# Sequantial_Cell_Switching.net
KiCad netlist of a schematic drawn in Altium Designer
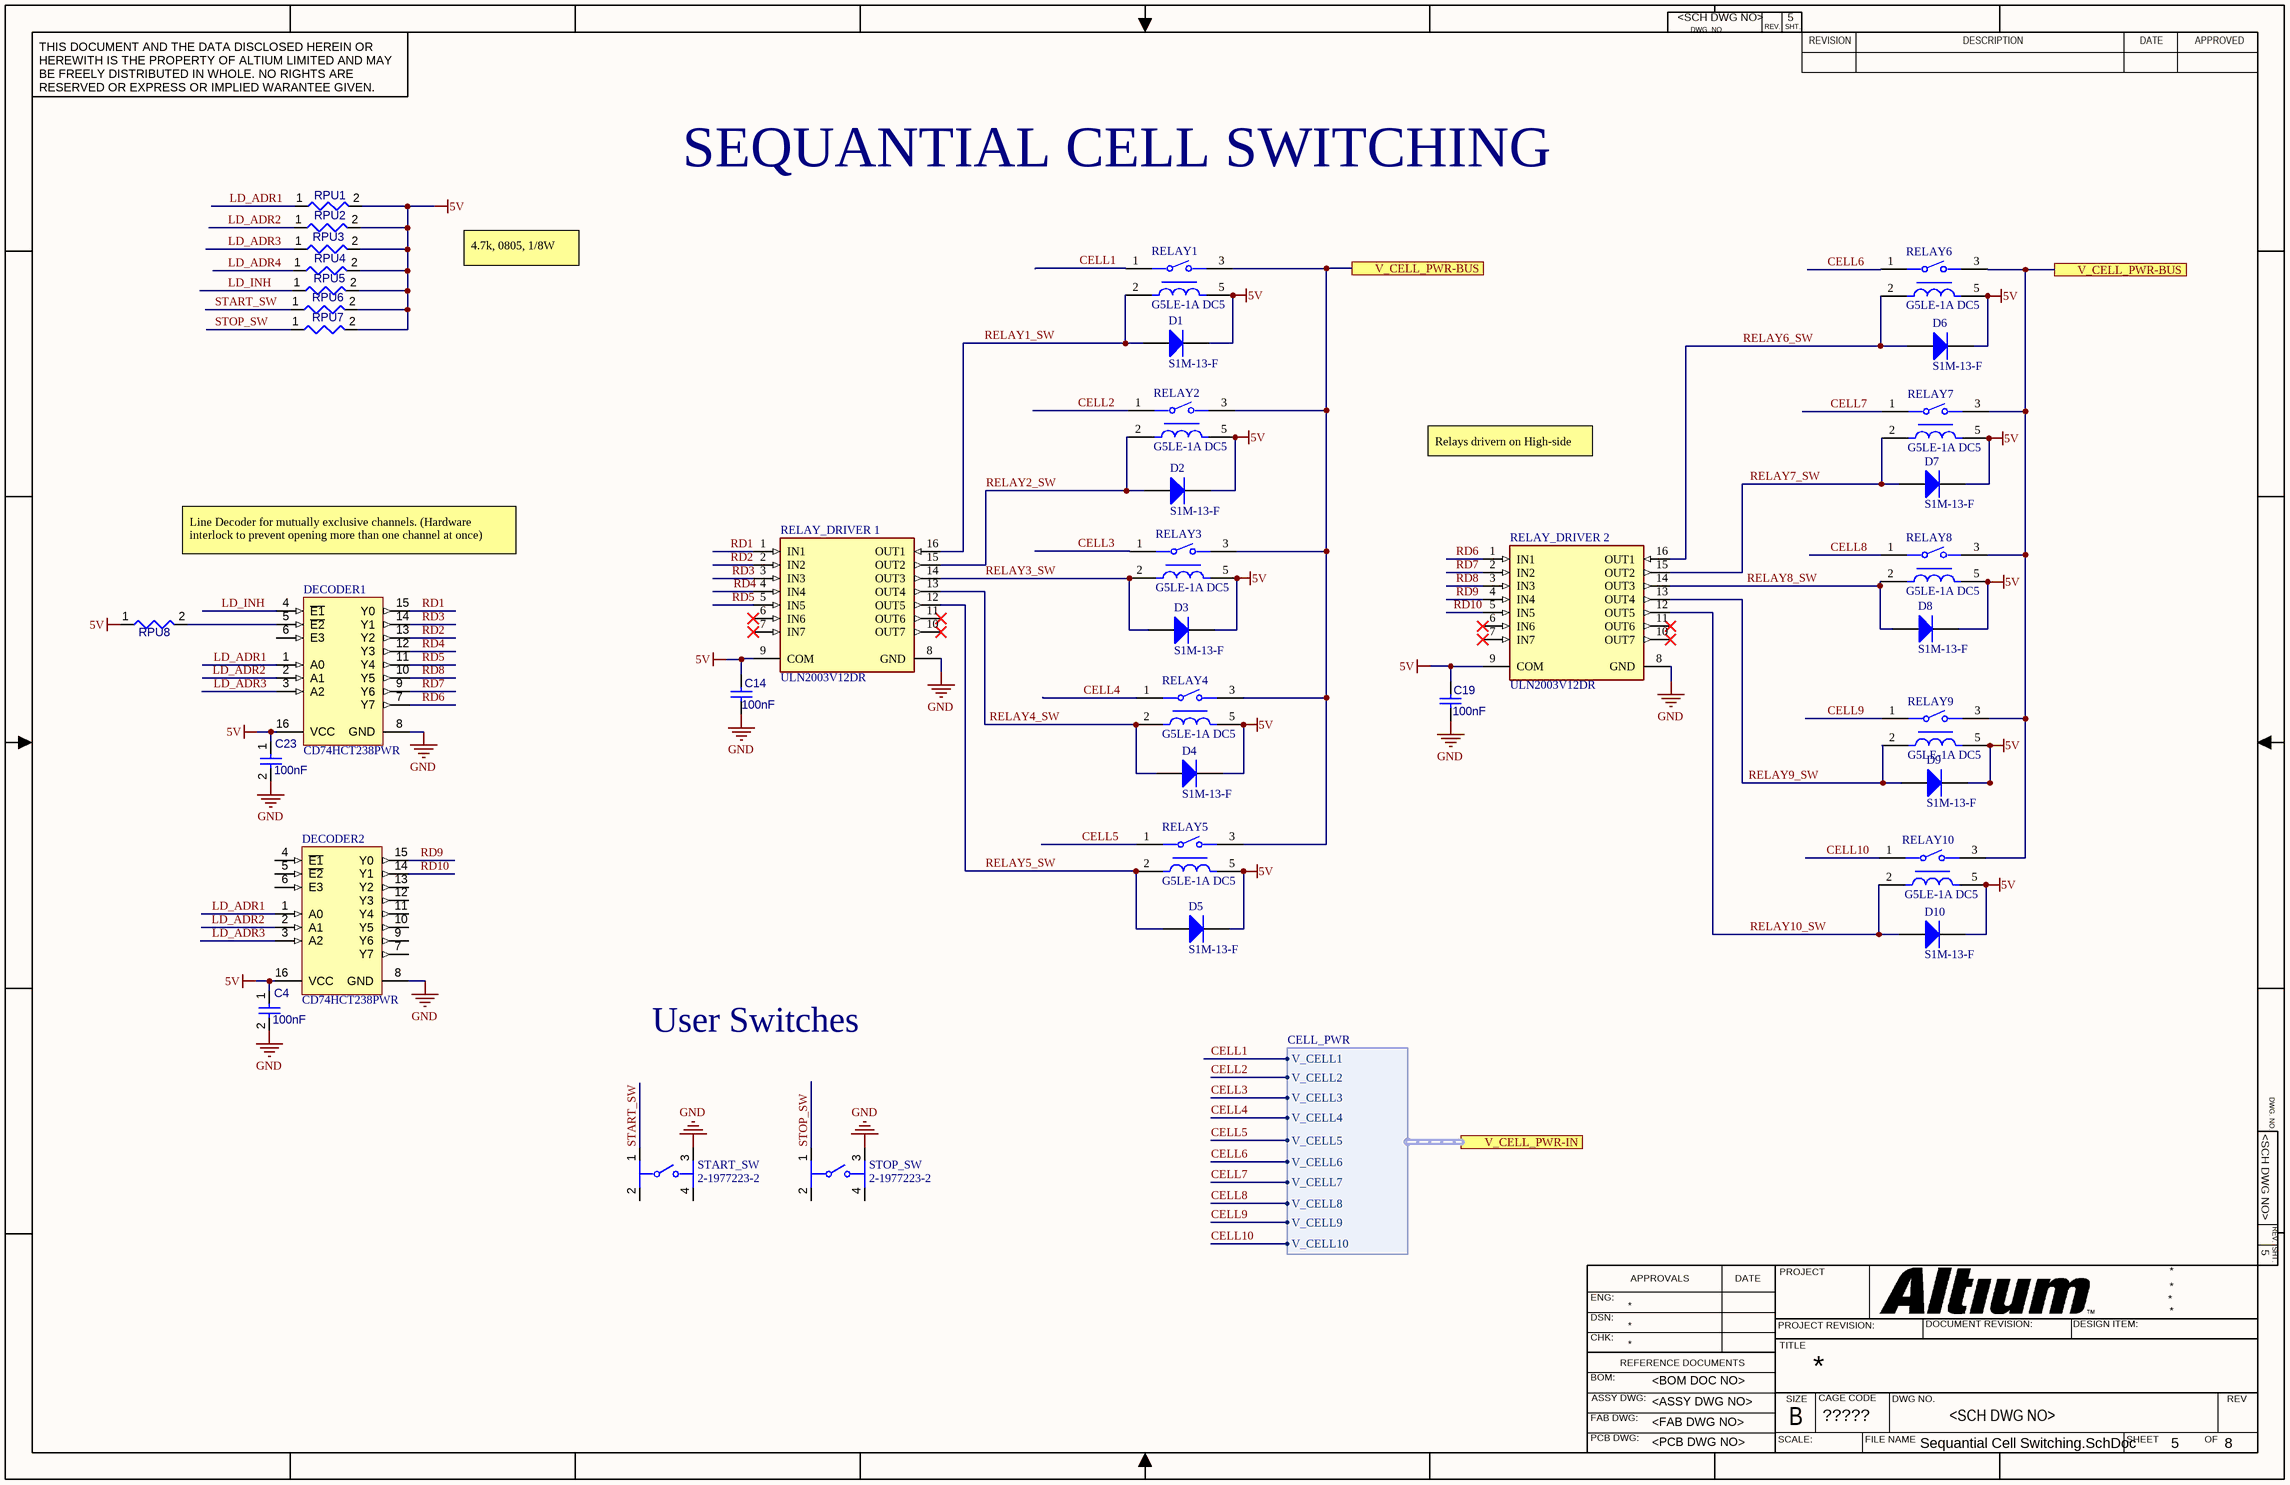
[diagram p0: Sequantial Cell Switching.SchDoc]

(export (version "E")
  (design (tool "Eeschema 10.0.6"))
  (components
    (comp (ref "C4")
      (value "100nF")
      (footprint "CAPC2013X95X50LL10T25")
      (description "Capacitor 100 nF +/-10% 50 V 0805")
      (fields (field (name "TOLERANCE") "10%"))
      (libsource (lib "gugan Sivakumar") (part "CAP-NP-2"))
    )
    (comp (ref "C14")
      (value "100nF")
      (footprint "CAPC2013X95X50LL10T25")
      (description "Capacitor 100 nF +/-10% 50 V 0805")
      (fields (field (name "TOLERANCE") "10%"))
      (libsource (lib "") (part "CAP-NP-2_1"))
    )
    (comp (ref "C19")
      (value "100nF")
      (footprint "CAPC2013X95X50LL10T25")
      (description "Capacitor 100 nF +/-10% 50 V 0805")
      (fields (field (name "TOLERANCE") "10%"))
      (libsource (lib "") (part "CAP-NP-2_1"))
    )
    (comp (ref "C23")
      (value "100nF")
      (footprint "CAPC2013X95X50LL10T25")
      (description "Capacitor 100 nF +/-10% 50 V 0805")
      (fields (field (name "TOLERANCE") "10%"))
      (libsource (lib "gugan Sivakumar") (part "CAP-NP-2"))
    )
    (comp (ref "D1")
      (value "S1M-13-F")
      (footprint "DIOD-S1M-13-F-SMA-2_V")
      (fields (field (name "MANUFACTURER") "Diodes Inc"))
      (libsource (lib "Altium Content Vault") (part "DIOD-D-A1K2-2"))
    )
    (comp (ref "D2")
      (value "S1M-13-F")
      (footprint "DIOD-S1M-13-F-SMA-2_V")
      (fields (field (name "MANUFACTURER") "Diodes Inc"))
      (libsource (lib "Altium Content Vault") (part "DIOD-D-A1K2-2"))
    )
    (comp (ref "D3")
      (value "S1M-13-F")
      (footprint "DIOD-S1M-13-F-SMA-2_V")
      (fields (field (name "MANUFACTURER") "Diodes Inc"))
      (libsource (lib "Altium Content Vault") (part "DIOD-D-A1K2-2"))
    )
    (comp (ref "D4")
      (value "S1M-13-F")
      (footprint "DIOD-S1M-13-F-SMA-2_V")
      (fields (field (name "MANUFACTURER") "Diodes Inc"))
      (libsource (lib "Altium Content Vault") (part "DIOD-D-A1K2-2"))
    )
    (comp (ref "D5")
      (value "S1M-13-F")
      (footprint "DIOD-S1M-13-F-SMA-2_V")
      (fields (field (name "MANUFACTURER") "Diodes Inc"))
      (libsource (lib "Altium Content Vault") (part "DIOD-D-A1K2-2"))
    )
    (comp (ref "D6")
      (value "S1M-13-F")
      (footprint "DIOD-S1M-13-F-SMA-2_V")
      (fields (field (name "MANUFACTURER") "Diodes Inc"))
      (libsource (lib "Altium Content Vault") (part "DIOD-D-A1K2-2"))
    )
    (comp (ref "D7")
      (value "S1M-13-F")
      (footprint "DIOD-S1M-13-F-SMA-2_V")
      (fields (field (name "MANUFACTURER") "Diodes Inc"))
      (libsource (lib "Altium Content Vault") (part "DIOD-D-A1K2-2"))
    )
    (comp (ref "D8")
      (value "S1M-13-F")
      (footprint "DIOD-S1M-13-F-SMA-2_V")
      (fields (field (name "MANUFACTURER") "Diodes Inc"))
      (libsource (lib "Altium Content Vault") (part "DIOD-D-A1K2-2"))
    )
    (comp (ref "D9")
      (value "S1M-13-F")
      (footprint "DIOD-S1M-13-F-SMA-2_V")
      (fields (field (name "MANUFACTURER") "Diodes Inc"))
      (libsource (lib "Altium Content Vault") (part "DIOD-D-A1K2-2"))
    )
    (comp (ref "D10")
      (value "S1M-13-F")
      (footprint "DIOD-S1M-13-F-SMA-2_V")
      (fields (field (name "MANUFACTURER") "Diodes Inc"))
      (libsource (lib "Altium Content Vault") (part "DIOD-D-A1K2-2"))
    )
    (comp (ref "DECODER1")
      (value "CD74HCT238PWR")
      (footprint "PW0016A_L")
      (fields
        (field (name "MANUFACTURER") "Texas Instruments")
        (field (name "GENERIC PART NUMBER") "CD74HCT238")
      )
      (libsource (lib "Altium Content Vault") (part "TI-CD54_74HCX238-16"))
    )
    (comp (ref "DECODER2")
      (value "CD74HCT238PWR")
      (footprint "PW0016A_L")
      (fields
        (field (name "MANUFACTURER") "Texas Instruments")
        (field (name "GENERIC PART NUMBER") "CD74HCT238")
      )
      (libsource (lib "Altium Content Vault") (part "TI-CD54_74HCX238-16"))
    )
    (comp (ref "RELAY1")
      (value "G5LE-1A DC5")
      (footprint "FP-G5LE-1A_DC5-MFG")
      (description "RELAY GEN PURPOSE SPST 10A 5V")
      (libsource (lib "Altium Content Vault") (part "6e495d724dc645a58f977e2129b87ff"))
    )
    (comp (ref "RELAY2")
      (value "G5LE-1A DC5")
      (footprint "FP-G5LE-1A_DC5-MFG")
      (description "RELAY GEN PURPOSE SPST 10A 5V")
      (libsource (lib "Altium Content Vault") (part "6e495d724dc645a58f977e2129b87ff"))
    )
    (comp (ref "RELAY3")
      (value "G5LE-1A DC5")
      (footprint "FP-G5LE-1A_DC5-MFG")
      (description "RELAY GEN PURPOSE SPST 10A 5V")
      (libsource (lib "Altium Content Vault") (part "6e495d724dc645a58f977e2129b87ff"))
    )
    (comp (ref "RELAY4")
      (value "G5LE-1A DC5")
      (footprint "FP-G5LE-1A_DC5-MFG")
      (description "RELAY GEN PURPOSE SPST 10A 5V")
      (libsource (lib "Altium Content Vault") (part "6e495d724dc645a58f977e2129b87ff"))
    )
    (comp (ref "RELAY5")
      (value "G5LE-1A DC5")
      (footprint "FP-G5LE-1A_DC5-MFG")
      (description "RELAY GEN PURPOSE SPST 10A 5V")
      (libsource (lib "Altium Content Vault") (part "6e495d724dc645a58f977e2129b87ff"))
    )
    (comp (ref "RELAY6")
      (value "G5LE-1A DC5")
      (footprint "FP-G5LE-1A_DC5-MFG")
      (description "RELAY GEN PURPOSE SPST 10A 5V")
      (libsource (lib "Altium Content Vault") (part "6e495d724dc645a58f977e2129b87ff"))
    )
    (comp (ref "RELAY7")
      (value "G5LE-1A DC5")
      (footprint "FP-G5LE-1A_DC5-MFG")
      (description "RELAY GEN PURPOSE SPST 10A 5V")
      (libsource (lib "Altium Content Vault") (part "6e495d724dc645a58f977e2129b87ff"))
    )
    (comp (ref "RELAY8")
      (value "G5LE-1A DC5")
      (footprint "FP-G5LE-1A_DC5-MFG")
      (description "RELAY GEN PURPOSE SPST 10A 5V")
      (libsource (lib "Altium Content Vault") (part "6e495d724dc645a58f977e2129b87ff"))
    )
    (comp (ref "RELAY9")
      (value "G5LE-1A DC5")
      (footprint "FP-G5LE-1A_DC5-MFG")
      (description "RELAY GEN PURPOSE SPST 10A 5V")
      (libsource (lib "Altium Content Vault") (part "6e495d724dc645a58f977e2129b87ff"))
    )
    (comp (ref "RELAY10")
      (value "G5LE-1A DC5")
      (footprint "FP-G5LE-1A_DC5-MFG")
      (description "RELAY GEN PURPOSE SPST 10A 5V")
      (libsource (lib "Altium Content Vault") (part "6e495d724dc645a58f977e2129b87ff"))
    )
    (comp (ref "RELAY_DRIVER 1")
      (value "ULN2003V12DR")
      (footprint "FP-D0016A-MFG")
      (description "MOSFET 7CH 16SOIC")
      (libsource (lib "Altium Content Vault") (part "1bf5c18f3aeaca83cb90dec63c1b343"))
    )
    (comp (ref "RELAY_DRIVER 2")
      (value "ULN2003V12DR")
      (footprint "FP-D0016A-MFG")
      (description "MOSFET 7CH 16SOIC")
      (libsource (lib "Altium Content Vault") (part "1bf5c18f3aeaca83cb90dec63c1b343"))
    )
    (comp (ref "RPU1")
      (value "Resistor 4k7 +/-1% 0805 125 mW")
      (footprint "RESC2013X70X40ML20T20")
      (description "Chip Resistor, 4.7 KOhm, +/- 1%, 0.125 W, -55 to 155 degC, 0805 (2012 Metric)")
      (fields (field (name "TOLERANCE") "1%") (field (name "POWER") "125mW"))
      (libsource (lib "gugan Sivakumar") (part "RES-2"))
    )
    (comp (ref "RPU2")
      (value "Resistor 4k7 +/-1% 0805 125 mW")
      (footprint "RESC2013X70X40ML20T20")
      (description "Chip Resistor, 4.7 KOhm, +/- 1%, 0.125 W, -55 to 155 degC, 0805 (2012 Metric)")
      (fields (field (name "TOLERANCE") "1%") (field (name "POWER") "125mW"))
      (libsource (lib "gugan Sivakumar") (part "RES-2"))
    )
    (comp (ref "RPU3")
      (value "Resistor 4k7 +/-1% 0805 125 mW")
      (footprint "RESC2013X70X40ML20T20")
      (description "Chip Resistor, 4.7 KOhm, +/- 1%, 0.125 W, -55 to 155 degC, 0805 (2012 Metric)")
      (fields (field (name "TOLERANCE") "1%") (field (name "POWER") "125mW"))
      (libsource (lib "gugan Sivakumar") (part "RES-2"))
    )
    (comp (ref "RPU4")
      (value "Resistor 4k7 +/-1% 0805 125 mW")
      (footprint "RESC2013X70X40ML20T20")
      (description "Chip Resistor, 4.7 KOhm, +/- 1%, 0.125 W, -55 to 155 degC, 0805 (2012 Metric)")
      (fields (field (name "TOLERANCE") "1%") (field (name "POWER") "125mW"))
      (libsource (lib "gugan Sivakumar") (part "RES-2"))
    )
    (comp (ref "RPU5")
      (value "Resistor 4k7 +/-1% 0805 125 mW")
      (footprint "RESC2013X70X40ML20T20")
      (description "Chip Resistor, 4.7 KOhm, +/- 1%, 0.125 W, -55 to 155 degC, 0805 (2012 Metric)")
      (fields (field (name "TOLERANCE") "1%") (field (name "POWER") "125mW"))
      (libsource (lib "gugan Sivakumar") (part "RES-2"))
    )
    (comp (ref "RPU6")
      (value "Resistor 4k7 +/-1% 0805 125 mW")
      (footprint "RESC2013X70X40ML20T20")
      (description "Chip Resistor, 4.7 KOhm, +/- 1%, 0.125 W, -55 to 155 degC, 0805 (2012 Metric)")
      (fields (field (name "TOLERANCE") "1%") (field (name "POWER") "125mW"))
      (libsource (lib "gugan Sivakumar") (part "RES-2"))
    )
    (comp (ref "RPU7")
      (value "Resistor 4k7 +/-1% 0805 125 mW")
      (footprint "RESC2013X70X40ML20T20")
      (description "Chip Resistor, 4.7 KOhm, +/- 1%, 0.125 W, -55 to 155 degC, 0805 (2012 Metric)")
      (fields (field (name "TOLERANCE") "1%") (field (name "POWER") "125mW"))
      (libsource (lib "gugan Sivakumar") (part "RES-2"))
    )
    (comp (ref "RPU8")
      (value "Resistor 4k7 +/-1% 0805 125 mW")
      (footprint "RESC2013X70X40ML20T20")
      (description "Chip Resistor, 4.7 KOhm, +/- 1%, 0.125 W, -55 to 155 degC, 0805 (2012 Metric)")
      (fields (field (name "TOLERANCE") "1%") (field (name "POWER") "125mW"))
      (libsource (lib "gugan Sivakumar") (part "RES-2"))
    )
    (comp (ref "START_SW")
      (value "2-1977223-2")
      (footprint "FP-2-1977223-2-MFG")
      (description "SWITCH TACTILE SPST-NO 0.05A 24V")
      (libsource (lib "Altium Content Vault") (part "b8895f3f4cefb76e1819d2863dba89b"))
    )
    (comp (ref "STOP_SW")
      (value "2-1977223-2")
      (footprint "FP-2-1977223-2-MFG")
      (description "SWITCH TACTILE SPST-NO 0.05A 24V")
      (libsource (lib "Altium Content Vault") (part "b8895f3f4cefb76e1819d2863dba89b"))
    )
  )
  (nets
    (net (code "2") (name "/CELL1") (class "Default")
      (node (ref "RELAY1") (pin "1") (pinfunction "1_1") (pintype "passive"))
    )
    (net (code "3") (name "/CELL2") (class "Default")
      (node (ref "RELAY2") (pin "1") (pinfunction "1_1") (pintype "passive"))
    )
    (net (code "4") (name "/CELL3") (class "Default")
      (node (ref "RELAY3") (pin "1") (pinfunction "1_1") (pintype "passive"))
    )
    (net (code "5") (name "/CELL4") (class "Default")
      (node (ref "RELAY4") (pin "1") (pinfunction "1_1") (pintype "passive"))
    )
    (net (code "6") (name "/CELL5") (class "Default")
      (node (ref "RELAY5") (pin "1") (pinfunction "1_1") (pintype "passive"))
    )
    (net (code "7") (name "/CELL6") (class "Default")
      (node (ref "RELAY6") (pin "1") (pinfunction "1_1") (pintype "passive"))
    )
    (net (code "8") (name "/CELL7") (class "Default")
      (node (ref "RELAY7") (pin "1") (pinfunction "1_1") (pintype "passive"))
    )
    (net (code "9") (name "/CELL8") (class "Default")
      (node (ref "RELAY8") (pin "1") (pinfunction "1_1") (pintype "passive"))
    )
    (net (code "10") (name "/CELL9") (class "Default")
      (node (ref "RELAY9") (pin "1") (pinfunction "1_1") (pintype "passive"))
    )
    (net (code "11") (name "/CELL10") (class "Default")
      (node (ref "RELAY10") (pin "1") (pinfunction "1_1") (pintype "passive"))
    )
    (net (code "12") (name "/LD_ADR1") (class "Default")
      (node (ref "DECODER1") (pin "1") (pinfunction "A0_1") (pintype "input"))
      (node (ref "DECODER2") (pin "1") (pinfunction "A0_1") (pintype "input"))
      (node (ref "RPU1") (pin "1") (pinfunction "1_1") (pintype "passive"))
    )
    (net (code "13") (name "/LD_ADR2") (class "Default")
      (node (ref "DECODER1") (pin "2") (pinfunction "A1_2") (pintype "input"))
      (node (ref "DECODER2") (pin "2") (pinfunction "A1_2") (pintype "input"))
      (node (ref "RPU2") (pin "1") (pinfunction "1_1") (pintype "passive"))
    )
    (net (code "14") (name "/LD_ADR3") (class "Default")
      (node (ref "DECODER1") (pin "3") (pinfunction "A2_3") (pintype "input"))
      (node (ref "DECODER2") (pin "3") (pinfunction "A2_3") (pintype "input"))
      (node (ref "RPU3") (pin "1") (pinfunction "1_1") (pintype "passive"))
    )
    (net (code "15") (name "/LD_ADR4") (class "Default")
      (node (ref "RPU4") (pin "1") (pinfunction "1_1") (pintype "passive"))
    )
    (net (code "16") (name "/LD_INH") (class "Default")
      (node (ref "DECODER1") (pin "4") (pinfunction "~{E1}_4") (pintype "input"))
      (node (ref "RPU5") (pin "1") (pinfunction "1_1") (pintype "passive"))
    )
    (net (code "17") (name "/RD1") (class "Default")
      (node (ref "DECODER1") (pin "15") (pinfunction "Y0_15") (pintype "output"))
      (node (ref "RELAY_DRIVER 1") (pin "1") (pinfunction "IN1_1") (pintype "input"))
    )
    (net (code "18") (name "/RD2") (class "Default")
      (node (ref "DECODER1") (pin "13") (pinfunction "Y2_13") (pintype "output"))
      (node (ref "RELAY_DRIVER 1") (pin "2") (pinfunction "IN2_2") (pintype "input"))
    )
    (net (code "19") (name "/RD3") (class "Default")
      (node (ref "DECODER1") (pin "14") (pinfunction "Y1_14") (pintype "output"))
      (node (ref "RELAY_DRIVER 1") (pin "3") (pinfunction "IN3_3") (pintype "input"))
    )
    (net (code "20") (name "/RD4") (class "Default")
      (node (ref "DECODER1") (pin "12") (pinfunction "Y3_12") (pintype "output"))
      (node (ref "RELAY_DRIVER 1") (pin "4") (pinfunction "IN4_4") (pintype "input"))
    )
    (net (code "21") (name "/RD5") (class "Default")
      (node (ref "DECODER1") (pin "11") (pinfunction "Y4_11") (pintype "output"))
      (node (ref "RELAY_DRIVER 1") (pin "5") (pinfunction "IN5_5") (pintype "input"))
    )
    (net (code "22") (name "/RD6") (class "Default")
      (node (ref "DECODER1") (pin "7") (pinfunction "Y7_7") (pintype "output"))
      (node (ref "RELAY_DRIVER 2") (pin "1") (pinfunction "IN1_1") (pintype "input"))
    )
    (net (code "23") (name "/RD7") (class "Default")
      (node (ref "DECODER1") (pin "9") (pinfunction "Y6_9") (pintype "output"))
      (node (ref "RELAY_DRIVER 2") (pin "2") (pinfunction "IN2_2") (pintype "input"))
    )
    (net (code "24") (name "/RD8") (class "Default")
      (node (ref "DECODER1") (pin "10") (pinfunction "Y5_10") (pintype "output"))
      (node (ref "RELAY_DRIVER 2") (pin "3") (pinfunction "IN3_3") (pintype "input"))
    )
    (net (code "25") (name "/RD9") (class "Default")
      (node (ref "DECODER2") (pin "15") (pinfunction "Y0_15") (pintype "output"))
      (node (ref "RELAY_DRIVER 2") (pin "4") (pinfunction "IN4_4") (pintype "input"))
    )
    (net (code "26") (name "/RD10") (class "Default")
      (node (ref "DECODER2") (pin "14") (pinfunction "Y1_14") (pintype "output"))
      (node (ref "RELAY_DRIVER 2") (pin "5") (pinfunction "IN5_5") (pintype "input"))
    )
    (net (code "27") (name "/RELAY1_SW") (class "Default")
      (node (ref "D1") (pin "1") (pinfunction "A_1") (pintype "passive"))
      (node (ref "RELAY1") (pin "2") (pinfunction "2_2") (pintype "passive"))
      (node (ref "RELAY_DRIVER 1") (pin "16") (pinfunction "OUT1_16") (pintype "input"))
    )
    (net (code "28") (name "/RELAY2_SW") (class "Default")
      (node (ref "D2") (pin "1") (pinfunction "A_1") (pintype "passive"))
      (node (ref "RELAY2") (pin "2") (pinfunction "2_2") (pintype "passive"))
      (node (ref "RELAY_DRIVER 1") (pin "15") (pinfunction "OUT2_15") (pintype "output"))
    )
    (net (code "29") (name "/RELAY3_SW") (class "Default")
      (node (ref "D3") (pin "1") (pinfunction "A_1") (pintype "passive"))
      (node (ref "RELAY3") (pin "2") (pinfunction "2_2") (pintype "passive"))
      (node (ref "RELAY_DRIVER 1") (pin "14") (pinfunction "OUT3_14") (pintype "output"))
    )
    (net (code "30") (name "/RELAY4_SW") (class "Default")
      (node (ref "D4") (pin "1") (pinfunction "A_1") (pintype "passive"))
      (node (ref "RELAY4") (pin "2") (pinfunction "2_2") (pintype "passive"))
      (node (ref "RELAY_DRIVER 1") (pin "13") (pinfunction "OUT4_13") (pintype "output"))
    )
    (net (code "31") (name "/RELAY5_SW") (class "Default")
      (node (ref "D5") (pin "1") (pinfunction "A_1") (pintype "passive"))
      (node (ref "RELAY5") (pin "2") (pinfunction "2_2") (pintype "passive"))
      (node (ref "RELAY_DRIVER 1") (pin "12") (pinfunction "OUT5_12") (pintype "output"))
    )
    (net (code "32") (name "/RELAY6_SW") (class "Default")
      (node (ref "D6") (pin "1") (pinfunction "A_1") (pintype "passive"))
      (node (ref "RELAY6") (pin "2") (pinfunction "2_2") (pintype "passive"))
      (node (ref "RELAY_DRIVER 2") (pin "16") (pinfunction "OUT1_16") (pintype "input"))
    )
    (net (code "33") (name "/RELAY7_SW") (class "Default")
      (node (ref "D7") (pin "1") (pinfunction "A_1") (pintype "passive"))
      (node (ref "RELAY7") (pin "2") (pinfunction "2_2") (pintype "passive"))
      (node (ref "RELAY_DRIVER 2") (pin "15") (pinfunction "OUT2_15") (pintype "output"))
    )
    (net (code "34") (name "/RELAY8_SW") (class "Default")
      (node (ref "D8") (pin "1") (pinfunction "A_1") (pintype "passive"))
      (node (ref "RELAY8") (pin "2") (pinfunction "2_2") (pintype "passive"))
      (node (ref "RELAY_DRIVER 2") (pin "14") (pinfunction "OUT3_14") (pintype "output"))
    )
    (net (code "35") (name "/RELAY9_SW") (class "Default")
      (node (ref "D9") (pin "1") (pinfunction "A_1") (pintype "passive"))
      (node (ref "RELAY9") (pin "2") (pinfunction "2_2") (pintype "passive"))
      (node (ref "RELAY_DRIVER 2") (pin "13") (pinfunction "OUT4_13") (pintype "output"))
    )
    (net (code "36") (name "/RELAY10_SW") (class "Default")
      (node (ref "D10") (pin "1") (pinfunction "A_1") (pintype "passive"))
      (node (ref "RELAY10") (pin "2") (pinfunction "2_2") (pintype "passive"))
      (node (ref "RELAY_DRIVER 2") (pin "12") (pinfunction "OUT5_12") (pintype "output"))
    )
    (net (code "37") (name "/START_SW") (class "Default")
      (node (ref "RPU6") (pin "1") (pinfunction "1_1") (pintype "passive"))
      (node (ref "START_SW") (pin "1") (pinfunction "1_1") (pintype "passive"))
    )
    (net (code "38") (name "/STOP_SW") (class "Default")
      (node (ref "RPU7") (pin "1") (pinfunction "1_1") (pintype "passive"))
      (node (ref "STOP_SW") (pin "1") (pinfunction "1_1") (pintype "passive"))
    )
    (net (code "39") (name "/V_CELL_PWR-BUS") (class "Default")
      (node (ref "RELAY1") (pin "3") (pinfunction "3_3") (pintype "passive"))
      (node (ref "RELAY10") (pin "3") (pinfunction "3_3") (pintype "passive"))
      (node (ref "RELAY2") (pin "3") (pinfunction "3_3") (pintype "passive"))
      (node (ref "RELAY3") (pin "3") (pinfunction "3_3") (pintype "passive"))
      (node (ref "RELAY4") (pin "3") (pinfunction "3_3") (pintype "passive"))
      (node (ref "RELAY5") (pin "3") (pinfunction "3_3") (pintype "passive"))
      (node (ref "RELAY6") (pin "3") (pinfunction "3_3") (pintype "passive"))
      (node (ref "RELAY7") (pin "3") (pinfunction "3_3") (pintype "passive"))
      (node (ref "RELAY8") (pin "3") (pinfunction "3_3") (pintype "passive"))
      (node (ref "RELAY9") (pin "3") (pinfunction "3_3") (pintype "passive"))
    )
    (net (code "41") (name "5V") (class "Default")
      (node (ref "C14") (pin "2") (pinfunction "2_2") (pintype "passive"))
      (node (ref "C19") (pin "2") (pinfunction "2_2") (pintype "passive"))
      (node (ref "C23") (pin "1") (pinfunction "1_1") (pintype "passive"))
      (node (ref "C4") (pin "1") (pinfunction "1_1") (pintype "passive"))
      (node (ref "D1") (pin "2") (pinfunction "K_2") (pintype "passive"))
      (node (ref "D10") (pin "2") (pinfunction "K_2") (pintype "passive"))
      (node (ref "D2") (pin "2") (pinfunction "K_2") (pintype "passive"))
      (node (ref "D3") (pin "2") (pinfunction "K_2") (pintype "passive"))
      (node (ref "D4") (pin "2") (pinfunction "K_2") (pintype "passive"))
      (node (ref "D5") (pin "2") (pinfunction "K_2") (pintype "passive"))
      (node (ref "D6") (pin "2") (pinfunction "K_2") (pintype "passive"))
      (node (ref "D7") (pin "2") (pinfunction "K_2") (pintype "passive"))
      (node (ref "D8") (pin "2") (pinfunction "K_2") (pintype "passive"))
      (node (ref "D9") (pin "2") (pinfunction "K_2") (pintype "passive"))
      (node (ref "DECODER1") (pin "16") (pinfunction "VCC_16") (pintype "power_in"))
      (node (ref "DECODER2") (pin "16") (pinfunction "VCC_16") (pintype "power_in"))
      (node (ref "RELAY1") (pin "5") (pinfunction "5_5") (pintype "passive"))
      (node (ref "RELAY10") (pin "5") (pinfunction "5_5") (pintype "passive"))
      (node (ref "RELAY2") (pin "5") (pinfunction "5_5") (pintype "passive"))
      (node (ref "RELAY3") (pin "5") (pinfunction "5_5") (pintype "passive"))
      (node (ref "RELAY4") (pin "5") (pinfunction "5_5") (pintype "passive"))
      (node (ref "RELAY5") (pin "5") (pinfunction "5_5") (pintype "passive"))
      (node (ref "RELAY6") (pin "5") (pinfunction "5_5") (pintype "passive"))
      (node (ref "RELAY7") (pin "5") (pinfunction "5_5") (pintype "passive"))
      (node (ref "RELAY8") (pin "5") (pinfunction "5_5") (pintype "passive"))
      (node (ref "RELAY9") (pin "5") (pinfunction "5_5") (pintype "passive"))
      (node (ref "RELAY_DRIVER 1") (pin "9") (pinfunction "COM_9") (pintype "passive"))
      (node (ref "RELAY_DRIVER 2") (pin "9") (pinfunction "COM_9") (pintype "passive"))
      (node (ref "RPU1") (pin "2") (pinfunction "2_2") (pintype "passive"))
      (node (ref "RPU2") (pin "2") (pinfunction "2_2") (pintype "passive"))
      (node (ref "RPU3") (pin "2") (pinfunction "2_2") (pintype "passive"))
      (node (ref "RPU4") (pin "2") (pinfunction "2_2") (pintype "passive"))
      (node (ref "RPU5") (pin "2") (pinfunction "2_2") (pintype "passive"))
      (node (ref "RPU6") (pin "2") (pinfunction "2_2") (pintype "passive"))
      (node (ref "RPU7") (pin "2") (pinfunction "2_2") (pintype "passive"))
      (node (ref "RPU8") (pin "1") (pinfunction "1_1") (pintype "passive"))
    )
    (net (code "42") (name "GND") (class "Default")
      (node (ref "C14") (pin "1") (pinfunction "1_1") (pintype "passive"))
      (node (ref "C19") (pin "1") (pinfunction "1_1") (pintype "passive"))
      (node (ref "C23") (pin "2") (pinfunction "2_2") (pintype "passive"))
      (node (ref "C4") (pin "2") (pinfunction "2_2") (pintype "passive"))
      (node (ref "DECODER1") (pin "8") (pinfunction "GND_8") (pintype "power_in"))
      (node (ref "DECODER2") (pin "8") (pinfunction "GND_8") (pintype "power_in"))
      (node (ref "RELAY_DRIVER 1") (pin "8") (pinfunction "GND_8") (pintype "power_in"))
      (node (ref "RELAY_DRIVER 2") (pin "8") (pinfunction "GND_8") (pintype "power_in"))
      (node (ref "START_SW") (pin "3") (pinfunction "3_3") (pintype "passive"))
      (node (ref "STOP_SW") (pin "3") (pinfunction "3_3") (pintype "passive"))
    )
    (net (code "43") (name "Net-(DECODER1-~{E2})") (class "Default")
      (node (ref "DECODER1") (pin "5") (pinfunction "~{E2}_5") (pintype "input"))
      (node (ref "RPU8") (pin "2") (pinfunction "2_2") (pintype "passive"))
    )
    (net (code "44") (name "unconnected-(DECODER1-E3-Pad6)") (class "Default")
      (node (ref "DECODER1") (pin "6") (pinfunction "E3_6") (pintype "input"))
    )
    (net (code "45") (name "unconnected-(DECODER2-E3-Pad6)") (class "Default")
      (node (ref "DECODER2") (pin "6") (pinfunction "E3_6") (pintype "input"))
    )
    (net (code "46") (name "unconnected-(DECODER2-Y2-Pad13)") (class "Default")
      (node (ref "DECODER2") (pin "13") (pinfunction "Y2_13") (pintype "output"))
    )
    (net (code "47") (name "unconnected-(DECODER2-Y3-Pad12)") (class "Default")
      (node (ref "DECODER2") (pin "12") (pinfunction "Y3_12") (pintype "output"))
    )
    (net (code "48") (name "unconnected-(DECODER2-Y4-Pad11)") (class "Default")
      (node (ref "DECODER2") (pin "11") (pinfunction "Y4_11") (pintype "output"))
    )
    (net (code "49") (name "unconnected-(DECODER2-Y5-Pad10)") (class "Default")
      (node (ref "DECODER2") (pin "10") (pinfunction "Y5_10") (pintype "output"))
    )
    (net (code "50") (name "unconnected-(DECODER2-Y6-Pad9)") (class "Default")
      (node (ref "DECODER2") (pin "9") (pinfunction "Y6_9") (pintype "output"))
    )
    (net (code "51") (name "unconnected-(DECODER2-Y7-Pad7)") (class "Default")
      (node (ref "DECODER2") (pin "7") (pinfunction "Y7_7") (pintype "output"))
    )
    (net (code "52") (name "unconnected-(DECODER2-~{E1}-Pad4)") (class "Default")
      (node (ref "DECODER2") (pin "4") (pinfunction "~{E1}_4") (pintype "input"))
    )
    (net (code "53") (name "unconnected-(DECODER2-~{E2}-Pad5)") (class "Default")
      (node (ref "DECODER2") (pin "5") (pinfunction "~{E2}_5") (pintype "input"))
    )
    (net (code "54") (name "unconnected-(RELAY_DRIVER 1-IN6-Pad6)") (class "Default")
      (node (ref "RELAY_DRIVER 1") (pin "6") (pinfunction "IN6_6") (pintype "input+no_connect"))
    )
    (net (code "55") (name "unconnected-(RELAY_DRIVER 1-IN7-Pad7)") (class "Default")
      (node (ref "RELAY_DRIVER 1") (pin "7") (pinfunction "IN7_7") (pintype "input+no_connect"))
    )
    (net (code "56") (name "unconnected-(RELAY_DRIVER 1-OUT6-Pad11)") (class "Default")
      (node (ref "RELAY_DRIVER 1") (pin "11") (pinfunction "OUT6_11") (pintype "output+no_connect"))
    )
    (net (code "57") (name "unconnected-(RELAY_DRIVER 1-OUT7-Pad10)") (class "Default")
      (node (ref "RELAY_DRIVER 1") (pin "10") (pinfunction "OUT7_10") (pintype "output+no_connect"))
    )
    (net (code "58") (name "unconnected-(RELAY_DRIVER 2-IN6-Pad6)") (class "Default")
      (node (ref "RELAY_DRIVER 2") (pin "6") (pinfunction "IN6_6") (pintype "input+no_connect"))
    )
    (net (code "59") (name "unconnected-(RELAY_DRIVER 2-IN7-Pad7)") (class "Default")
      (node (ref "RELAY_DRIVER 2") (pin "7") (pinfunction "IN7_7") (pintype "input+no_connect"))
    )
    (net (code "60") (name "unconnected-(RELAY_DRIVER 2-OUT6-Pad11)") (class "Default")
      (node (ref "RELAY_DRIVER 2") (pin "11") (pinfunction "OUT6_11") (pintype "output+no_connect"))
    )
    (net (code "61") (name "unconnected-(RELAY_DRIVER 2-OUT7-Pad10)") (class "Default")
      (node (ref "RELAY_DRIVER 2") (pin "10") (pinfunction "OUT7_10") (pintype "output+no_connect"))
    )
    (net (code "62") (name "unconnected-(START_SW-Pad2)") (class "Default")
      (node (ref "START_SW") (pin "2") (pinfunction "2_2") (pintype "passive"))
    )
    (net (code "63") (name "unconnected-(START_SW-Pad4)") (class "Default")
      (node (ref "START_SW") (pin "4") (pinfunction "4_4") (pintype "passive"))
    )
    (net (code "64") (name "unconnected-(STOP_SW-Pad2)") (class "Default")
      (node (ref "STOP_SW") (pin "2") (pinfunction "2_2") (pintype "passive"))
    )
    (net (code "65") (name "unconnected-(STOP_SW-Pad4)") (class "Default")
      (node (ref "STOP_SW") (pin "4") (pinfunction "4_4") (pintype "passive"))
    )
  )
)
